# Current_Driver_1.net
KiCad netlist of a schematic drawn in Altium Designer
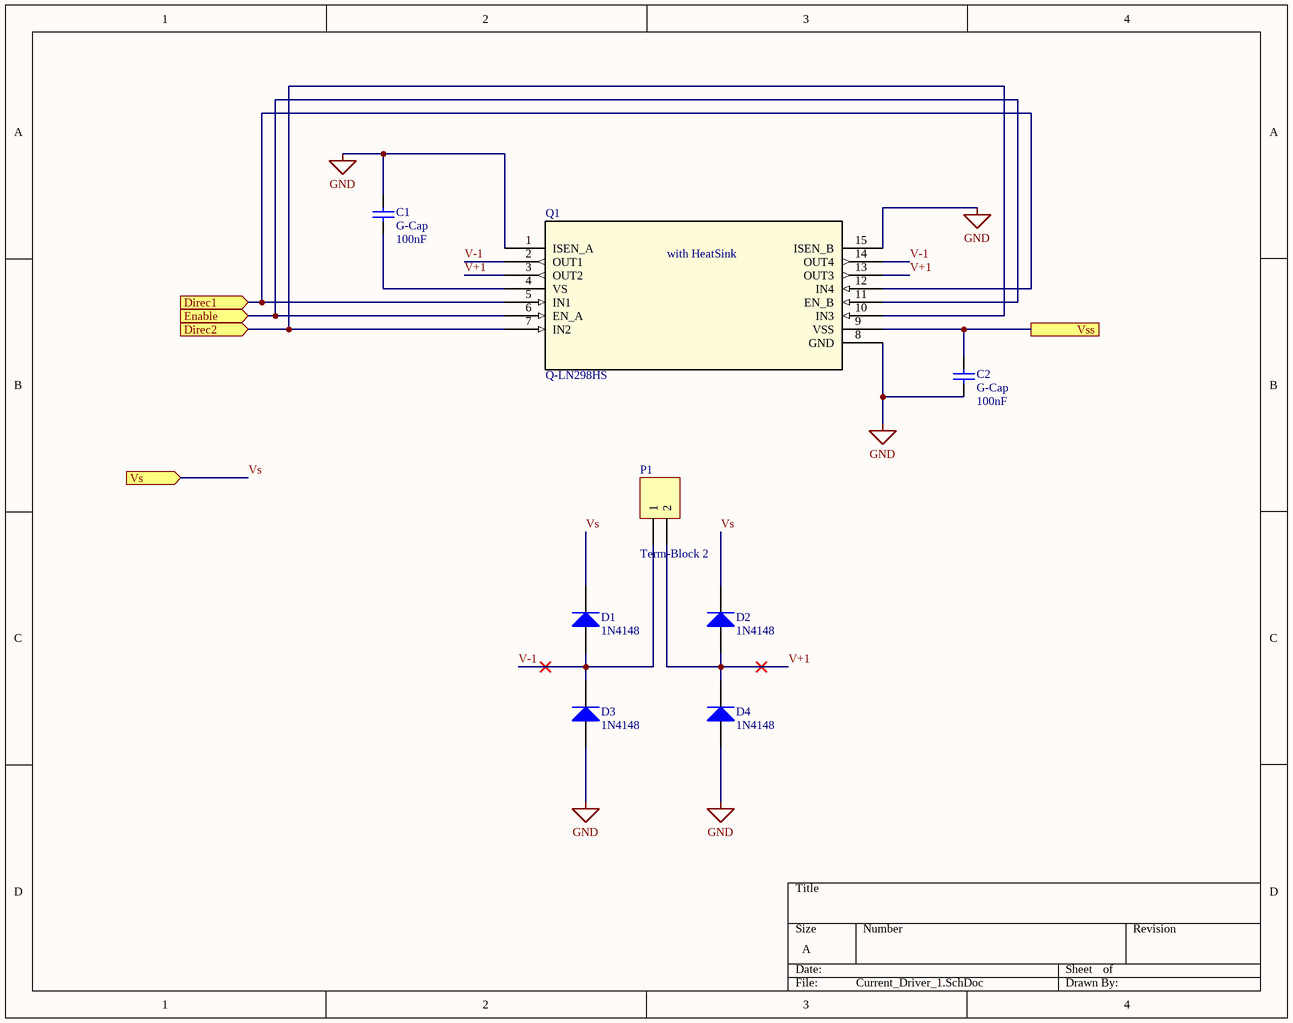
[diagram p0: Current_Driver_1.SchDoc]

(export (version "E")
  (design (tool "Eeschema 10.0.6"))
  (components
    (comp (ref "C1")
      (value "G-Cap")
      (footprint "Cap2.54mm_LGE1.0")
      (description "Capacitor (specify value)")
      (fields (field (name "ALTIUM_VALUE") "100nF") (field (name "PUBLISHER") "Altium Limited"))
      (libsource (lib "PartsDatabaseV16.1") (part "G-Cap"))
    )
    (comp (ref "C2")
      (value "G-Cap")
      (footprint "Cap2.54mm_LGE1.0")
      (description "Capacitor (specify value)")
      (fields (field (name "ALTIUM_VALUE") "100nF") (field (name "PUBLISHER") "Altium Limited"))
      (libsource (lib "PartsDatabaseV16.1") (part "G-Cap"))
    )
    (comp (ref "D1")
      (value "1N4148")
      (footprint "DO-41_XLGE1.2")
      (description "High-speed Diode")
      (libsource (lib "PartsDatabaseV16.1") (part "T-DiodeRect"))
    )
    (comp (ref "D2")
      (value "1N4148")
      (footprint "DO-41_XLGE1.2")
      (description "High-speed Diode")
      (libsource (lib "PartsDatabaseV16.1") (part "T-DiodeRect"))
    )
    (comp (ref "D3")
      (value "1N4148")
      (footprint "DO-41_XLGE1.2")
      (description "High-speed Diode")
      (libsource (lib "PartsDatabaseV16.1") (part "T-DiodeRect"))
    )
    (comp (ref "D4")
      (value "1N4148")
      (footprint "DO-41_XLGE1.2")
      (description "High-speed Diode")
      (libsource (lib "PartsDatabaseV16.1") (part "T-DiodeRect"))
    )
    (comp (ref "P1")
      (value "Term-Block 2")
      (footprint "TERM-BLOCK-5.08MM-2POS")
      (description "Terminal-Block 1x2")
      (fields (field (name "PUBLISHER") "Altium Limited"))
      (libsource (lib "PartsDatabaseV16.1") (part "C-Block2"))
    )
    (comp (ref "Q1")
      (value "Q-LN298HS")
      (footprint "Multiwatt15_V_ELEC391HS")
      (description "LN298 - IC Bridge Driver Par 15Multiwatt")
      (fields
        (field (name "MANUFACTURER_PART_NUMBER") "L298N")
        (field (name "COPYRIGHT") "Copyright (C) 2015 Accelerated Designs. All rights reserved")
      )
      (libsource (lib "Additional Parts 391") (part "Q-LN298HS"))
    )
  )
  (nets
    (net (code "1") (name "/Direc1") (class "Default")
      (node (ref "Q1") (pin "12") (pinfunction "IN4_12") (pintype "input"))
      (node (ref "Q1") (pin "5") (pinfunction "IN1_5") (pintype "input"))
    )
    (net (code "2") (name "/Direc2") (class "Default")
      (node (ref "Q1") (pin "10") (pinfunction "IN3_10") (pintype "input"))
      (node (ref "Q1") (pin "7") (pinfunction "IN2_7") (pintype "input"))
    )
    (net (code "3") (name "/Enable") (class "Default")
      (node (ref "Q1") (pin "11") (pinfunction "EN_B_11") (pintype "input"))
      (node (ref "Q1") (pin "6") (pinfunction "EN_A_6") (pintype "input"))
    )
    (net (code "4") (name "/V+1") (class "Default")
      (node (ref "D2") (pin "1") (pinfunction "A_1") (pintype "passive"))
      (node (ref "D4") (pin "2") (pinfunction "K_2") (pintype "passive"))
      (node (ref "P1") (pin "2") (pinfunction "2_2") (pintype "passive"))
      (node (ref "Q1") (pin "13") (pinfunction "OUT3_13") (pintype "output"))
      (node (ref "Q1") (pin "3") (pinfunction "OUT2_3") (pintype "output"))
    )
    (net (code "5") (name "/V-1") (class "Default")
      (node (ref "D1") (pin "1") (pinfunction "A_1") (pintype "passive"))
      (node (ref "D3") (pin "2") (pinfunction "K_2") (pintype "passive"))
      (node (ref "P1") (pin "1") (pinfunction "1_1") (pintype "passive"))
      (node (ref "Q1") (pin "14") (pinfunction "OUT4_14") (pintype "output"))
      (node (ref "Q1") (pin "2") (pinfunction "OUT1_2") (pintype "output"))
    )
    (net (code "6") (name "/Vs") (class "Default")
      (node (ref "D1") (pin "2") (pinfunction "K_2") (pintype "passive"))
      (node (ref "D2") (pin "2") (pinfunction "K_2") (pintype "passive"))
    )
    (net (code "7") (name "/Vss") (class "Default")
      (node (ref "C2") (pin "2") (pinfunction "2_2") (pintype "passive"))
      (node (ref "Q1") (pin "9") (pinfunction "VSS_9") (pintype "power_in"))
    )
    (net (code "8") (name "GND") (class "Default")
      (node (ref "C1") (pin "2") (pinfunction "2_2") (pintype "passive"))
      (node (ref "C2") (pin "1") (pinfunction "1_1") (pintype "passive"))
      (node (ref "D3") (pin "1") (pinfunction "A_1") (pintype "passive"))
      (node (ref "D4") (pin "1") (pinfunction "A_1") (pintype "passive"))
      (node (ref "Q1") (pin "1") (pinfunction "ISEN_A_1") (pintype "passive"))
      (node (ref "Q1") (pin "15") (pinfunction "ISEN_B_15") (pintype "passive"))
      (node (ref "Q1") (pin "8") (pinfunction "GND_8") (pintype "power_in"))
    )
    (net (code "9") (name "Net-(Q1-VS)") (class "Default")
      (node (ref "C1") (pin "1") (pinfunction "1_1") (pintype "passive"))
      (node (ref "Q1") (pin "4") (pinfunction "VS_4") (pintype "power_in"))
    )
  )
)
